# Schematic_Rev2.net
KiCad netlist of a schematic drawn in Altium Designer
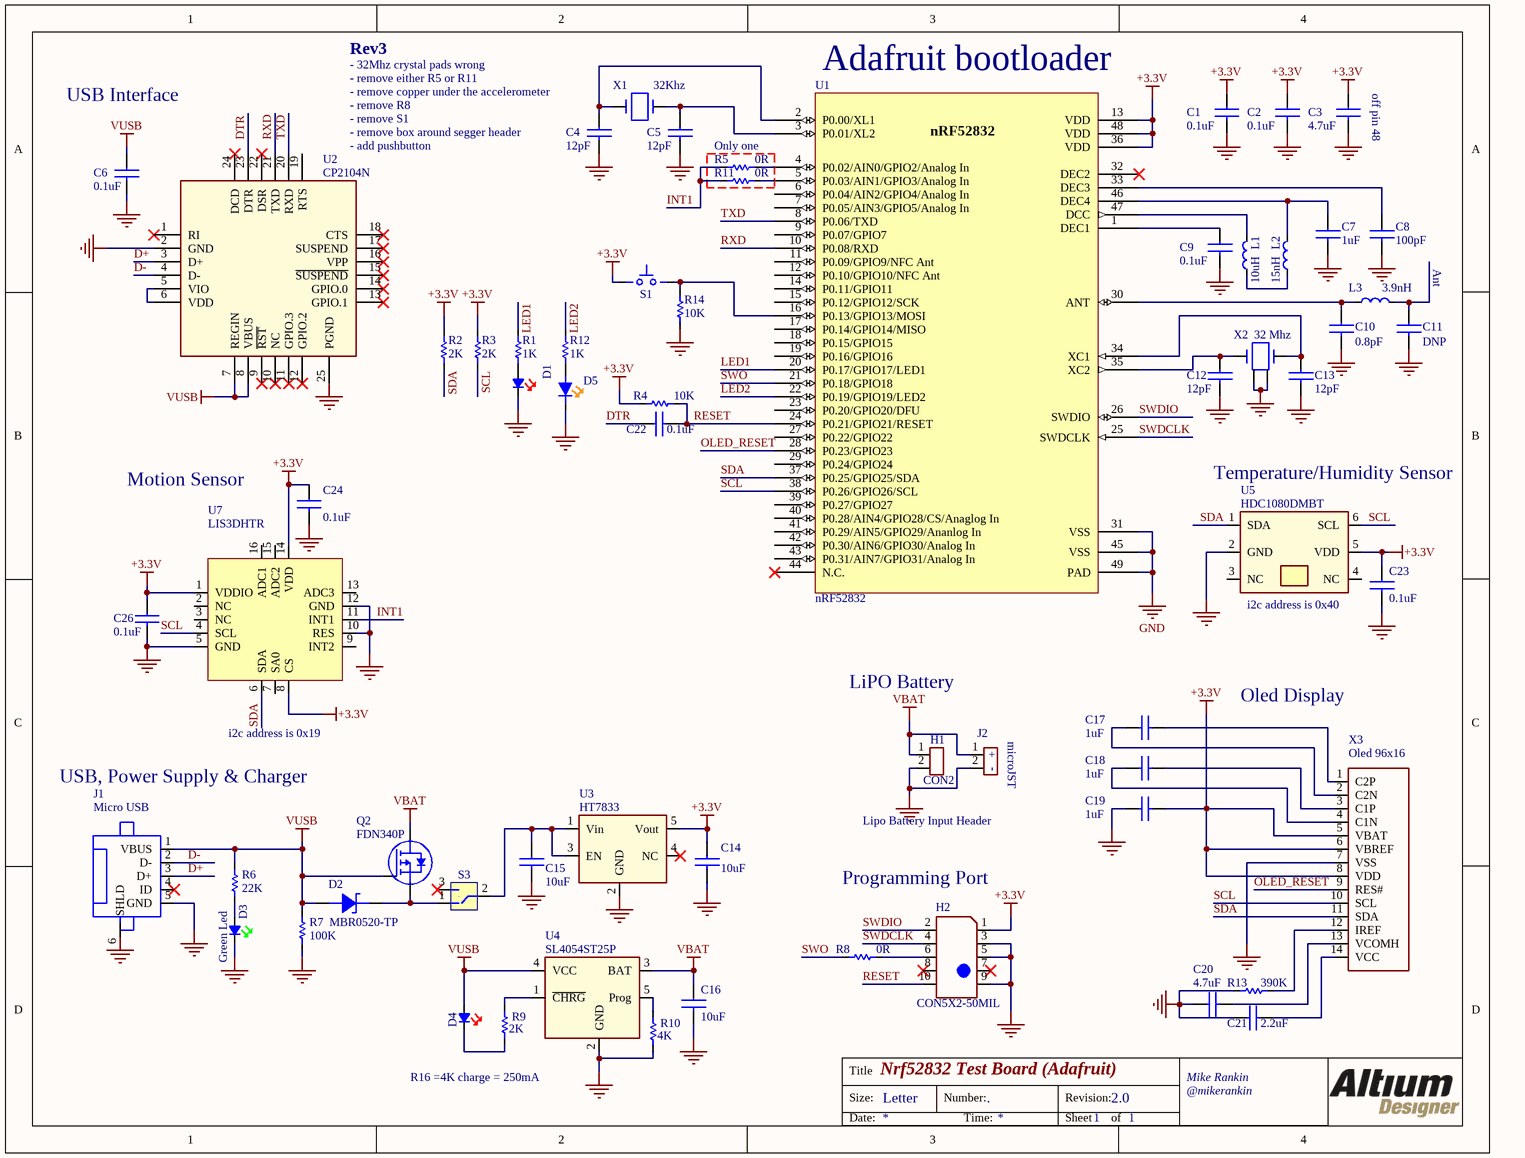
[diagram p0: Schematic_Rev2.SchDoc]

(export (version "E")
  (design (tool "Eeschema 10.0.6"))
  (components
    (comp (ref "C1")
      (value "0.1uF")
      (footprint "CAPC1005X56N")
      (description "CAP 0.1uF 0402")
      (libsource (lib "MAR") (part "CAP_0402"))
    )
    (comp (ref "C2")
      (value "0.1uF")
      (footprint "CAPC1005X56N")
      (description "CAP 0.1uF 0402")
      (libsource (lib "MAR") (part "CAP_0402"))
    )
    (comp (ref "C3")
      (value "4.7uF")
      (footprint "CAPC1005X56N")
      (description "CAP 4.7uF 0402")
      (libsource (lib "MAR") (part "CAP_0402"))
    )
    (comp (ref "C4")
      (value "12pF")
      (footprint "CAPC1005X56N")
      (description "CAP 12pF 0402")
      (libsource (lib "MAR") (part "CAP_0402"))
    )
    (comp (ref "C5")
      (value "12pF")
      (footprint "CAPC1005X56N")
      (description "CAP 12pF 0402")
      (libsource (lib "MAR") (part "CAP_0402"))
    )
    (comp (ref "C6")
      (value "0.1uF")
      (footprint "CAPC1005X56N")
      (description "CAP 0.1uF 0402")
      (libsource (lib "MAR") (part "CAP_0402"))
    )
    (comp (ref "C7")
      (value "1uF")
      (footprint "CAPC1005X56N")
      (description "CAP 1uF 0402")
      (libsource (lib "MAR") (part "CAP_0402"))
    )
    (comp (ref "C8")
      (value "100pF")
      (footprint "CAPC1005X56N")
      (description "CAP 100pF 0402")
      (libsource (lib "MAR") (part "CAP_0402"))
    )
    (comp (ref "C9")
      (value "0.1uF")
      (footprint "CAPC1005X56N")
      (description "CAP 0.1uF 0402")
      (libsource (lib "MAR") (part "CAP_0402"))
    )
    (comp (ref "C10")
      (value "0.8pF")
      (footprint "CAPC1005X56N")
      (description "CAP 0.8pF 0402")
      (libsource (lib "MAR") (part "CAP_0402"))
    )
    (comp (ref "C11")
      (value "DNP")
      (footprint "CAPC1005X56N")
      (description "CAP DNP 0402")
      (libsource (lib "MAR") (part "CAP_0402"))
    )
    (comp (ref "C12")
      (value "12pF")
      (footprint "CAPC1005X56N")
      (description "CAP 12pF 0402")
      (libsource (lib "MAR") (part "CAP_0402"))
    )
    (comp (ref "C13")
      (value "12pF")
      (footprint "CAPC1005X56N")
      (description "CAP 12pF 0402")
      (libsource (lib "MAR") (part "CAP_0402"))
    )
    (comp (ref "C14")
      (value "10uF")
      (footprint "CAPC2012X140N")
      (description "CAP 10uF 0805")
      (libsource (lib "MAR") (part "CAP_0805"))
    )
    (comp (ref "C15")
      (value "10uF")
      (footprint "CAPC2012X140N")
      (description "CAP 10uF 0805")
      (libsource (lib "MAR") (part "CAP_0805"))
    )
    (comp (ref "C16")
      (value "10uF")
      (footprint "CAPC2012X140N")
      (description "CAP 10uF 0805")
      (libsource (lib "MAR") (part "CAP_0805"))
    )
    (comp (ref "C17")
      (value "1uF")
      (footprint "CAPC1005X56N")
      (description "CAP 0.1uF 16V 0402")
      (fields (field (name "PART_NUMBER") "C29266") (field (name "MANUFACTURER") "Samsung"))
      (libsource (lib "MAR") (part "CAP_0402"))
    )
    (comp (ref "C18")
      (value "1uF")
      (footprint "CAPC1005X56N")
      (description "CAP 0.1uF 16V 0402")
      (fields (field (name "PART_NUMBER") "C29266") (field (name "MANUFACTURER") "Samsung"))
      (libsource (lib "MAR") (part "CAP_0402"))
    )
    (comp (ref "C19")
      (value "1uF")
      (footprint "CAPC1005X56N")
      (description "CAP 0.1uF 16V 0402")
      (fields (field (name "PART_NUMBER") "C29266") (field (name "MANUFACTURER") "Samsung"))
      (libsource (lib "MAR") (part "CAP_0402"))
    )
    (comp (ref "C20")
      (value "4.7uF")
      (footprint "CAPC1005X56N")
      (description "CAP 4.7uF 16V 0402")
      (fields (field (name "PART_NUMBER") "C318563") (field (name "MANUFACTURER") "Samsung"))
      (libsource (lib "MAR") (part "CAP_0402"))
    )
    (comp (ref "C21")
      (value "2.2uF")
      (footprint "CAPC1005X56N")
      (description "CAP 2.2uF 16V 0402")
      (fields (field (name "PART_NUMBER") "C170151") (field (name "MANUFACTURER") "Samsung"))
      (libsource (lib "MAR") (part "CAP_0402"))
    )
    (comp (ref "C22")
      (value "0.1uF")
      (footprint "CAPC1005X56N")
      (description "CAP 0.1uF 0402")
      (libsource (lib "MAR") (part "CAP_0402"))
    )
    (comp (ref "C23")
      (value "0.1uF")
      (footprint "CAPC1005X56N")
      (description "CAP 0.1uF 0402")
      (fields (field (name "PARTNUMBER") "TCC0402X5R104M160AT") (field (name "MANUFACTURER") "CCTC"))
      (libsource (lib "MAR") (part "CAP_0402"))
    )
    (comp (ref "C24")
      (value "0.1uF")
      (footprint "RESC1005X40L")
      (description "CAP 0.1uF 0402")
      (fields (field (name "PARTNUMBER") "C344190") (field (name "MANUFACTURER") "CCTC"))
      (libsource (lib "MAR") (part "CAP_0402"))
    )
    (comp (ref "C26")
      (value "0.1uF")
      (footprint "CAPC1005X56N")
      (description "CAP 0.1uF 0402")
      (fields (field (name "PARTNUMBER") "C344190") (field (name "MANUFACTURER") "CCTC"))
      (libsource (lib "MAR") (part "CAP_0402"))
    )
    (comp (ref "D1")
      (value "Red Led")
      (footprint "LED1608X55N-RED")
      (description "LED RED 0603")
      (libsource (lib "MAR") (part "LED_0603_SMALL_RED"))
    )
    (comp (ref "D2")
      (value "MBR0520-TP")
      (footprint "SOD123")
      (description "DIODE SCHOTTKY 20V 500MA SOD-123")
      (fields (field (name "MANUFACTURER") "Micro") (field (name "PART_NUMBER") "C78746"))
      (libsource (lib "MAR") (part "MBR0520-TP"))
    )
    (comp (ref "D3")
      (value "Green Led")
      (footprint "LED1608X55N-RED")
      (description "LED Green 0603")
      (libsource (lib "MAR") (part "LED_0603_SMALL_GREEN"))
    )
    (comp (ref "D4")
      (value "Red Led")
      (footprint "LED1608X55N-RED")
      (description "LED RED 0603")
      (libsource (lib "MAR") (part "LED_0603_SMALL_RED"))
    )
    (comp (ref "D5")
      (value "Orange Led")
      (footprint "LED1608X55N-YELLOW")
      (description "LED Orange 0603")
      (libsource (lib "MAR") (part "LED_0603_Orange"))
    )
    (comp (ref "H1")
      (value "CON2")
      (footprint "HDR1X2-EMPTY")
      (description "EMPTY SOLDER 2POS")
      (libsource (lib "MAR") (part "CON2-EMPTY_PAD"))
    )
    (comp (ref "H2")
      (value "CON5X2-50MIL")
      (footprint "HDR5X2-50MIL-SMT")
      (description "JTAG CONN HEADER 5X2POS 50mil\" PADS")
      (fields (field (name "PARTNUMBER") "PADS"))
      (libsource (lib "MAR") (part "CON5X2_50mil"))
    )
    (comp (ref "J1")
      (value "Micro USB")
      (footprint "U254-051N-4BH806")
      (description "CONN RECPT MICRO USB")
      (fields (field (name "MANUFACTURER") "XKB") (field (name "PART_NUMBER") "C319170"))
      (libsource (lib "MAR") (part "U254-051N-4BH806"))
    )
    (comp (ref "J2")
      (value "CON2")
      (footprint "JST_Micro_2PIN")
      (description "JST MIcro CONN 2POS")
      (libsource (lib "MAR") (part "JST_Micro_CONN_2PIN"))
    )
    (comp (ref "L1")
      (value "10uH")
      (footprint "RESC1608X06L")
      (description "INDUCTOR 10uH 900mA 0603")
      (fields (field (name "MANUFACTURER") "Murata"))
      (libsource (lib "MAR") (part "LQW15AN3N9D10D"))
    )
    (comp (ref "L2")
      (value "15nH")
      (footprint "INDC1005X40L")
      (description "INDUCTOR 15nH 900mA 0402")
      (libsource (lib "MAR") (part "LQW15AN3N9D10D"))
    )
    (comp (ref "L3")
      (value "3.9nH")
      (footprint "INDC1005X40L")
      (description "INDUCTOR 3.9nH 900mA 0402")
      (fields (field (name "PART_NUMBER") "C412344") (field (name "MANUFACTURER") "Murata"))
      (libsource (lib "MAR") (part "LQW15AN3N9D10D"))
    )
    (comp (ref "Q2")
      (value "FDN340P")
      (footprint "SOT95P240X110-3N")
      (description "MOSFET P-CH 20V 2A SOT-23")
      (fields (field (name "MANUFACTURER") "On Semi") (field (name "PART_NUMBER") "C75469"))
      (libsource (lib "MAR") (part "FDN340P"))
    )
    (comp (ref "R1")
      (value "1K")
      (footprint "RESC1005X40L")
      (description "RES 1K 0402")
      (libsource (lib "MAR") (part "RES_0402"))
    )
    (comp (ref "R2")
      (value "2K")
      (footprint "RESC1005X40L")
      (description "RES 2K 0402")
      (libsource (lib "MAR") (part "RES_0402"))
    )
    (comp (ref "R3")
      (value "2K")
      (footprint "RESC1005X40L")
      (description "RES 2K 0402")
      (libsource (lib "MAR") (part "RES_0402"))
    )
    (comp (ref "R4")
      (value "10K")
      (footprint "RESC1005X40L")
      (description "RES 10K 0402")
      (libsource (lib "MAR") (part "RES_0402"))
    )
    (comp (ref "R5")
      (value "0R")
      (footprint "RESC1005X40L")
      (description "RES 0R 0402")
      (libsource (lib "MAR") (part "RES_0402"))
    )
    (comp (ref "R6")
      (value "22K")
      (footprint "RESC1005X40L")
      (description "RES 22K 0402")
      (libsource (lib "MAR") (part "RES_0402"))
    )
    (comp (ref "R7")
      (value "100K")
      (footprint "RESC1005X40L")
      (description "RES 100K 0402")
      (libsource (lib "MAR") (part "RES_0402"))
    )
    (comp (ref "R8")
      (value "0R")
      (footprint "RESC1005X40L")
      (description "RES 0R 0402")
      (libsource (lib "MAR") (part "RES_0402"))
    )
    (comp (ref "R9")
      (value "2K")
      (footprint "RESC1005X40L")
      (description "RES 2K 0402")
      (libsource (lib "MAR") (part "RES_0402"))
    )
    (comp (ref "R10")
      (value "4K")
      (footprint "RESC1005X40L")
      (description "RES 4K 0402")
      (libsource (lib "MAR") (part "RES_0402"))
    )
    (comp (ref "R11")
      (value "0R")
      (footprint "RESC1005X40L")
      (description "RES 0R 0402")
      (libsource (lib "MAR") (part "RES_0402"))
    )
    (comp (ref "R12")
      (value "1K")
      (footprint "RESC1005X40L")
      (description "RES 1K 0402")
      (libsource (lib "MAR") (part "RES_0402"))
    )
    (comp (ref "R13")
      (value "390K")
      (footprint "RESC1005X40L")
      (description "RES 390K 0402")
      (fields (field (name "PART_NUMBER") "C25782") (field (name "MANUFACTURER") "Uniroyal"))
      (libsource (lib "MAR") (part "RES_0402"))
    )
    (comp (ref "R14")
      (value "10K")
      (footprint "RESC1005X40L")
      (description "RES 10K 0402")
      (libsource (lib "MAR") (part "RES_0402"))
    )
    (comp (ref "S1")
      (value "Pushbutton")
      (footprint "TL1015AF160QG")
      (description "Switch SMD,3x4x2.5mm")
      (fields (field (name "PART_NUMBER") "C455281") (field (name "MANUFACTURER") "Xunpu"))
      (libsource (lib "MAR") (part "TL1015AF160QG"))
    )
    (comp (ref "S3")
      (value "SWITCH SLIDE")
      (footprint "SK-3245D-02-L4")
      (description "Switch Slide Thu Hole")
      (fields (field (name "MANUFACTURER") "KXB Enterprise") (field (name "PARTNUMBER") "SK-3245D-02-L4"))
      (libsource (lib "MAR") (part "SK-3245D-02-L4"))
    )
    (comp (ref "U1")
      (value "nRF52832")
      (footprint "QFN48")
      (description "MCU Bluetooth 2.4GHz 48-VFQFN Exposed Pad")
      (fields (field (name "MANUFACTURER") "Nordic Semi") (field (name "PART_NUMBER") "C77540"))
      (libsource (lib "MAR") (part "nRF52832"))
    )
    (comp (ref "U2")
      (value "CP2104N")
      (footprint "24-QFN")
      (description "IC BRIDGE USB TO UART 24QFN")
      (fields (field (name "MANUFACTURER") "Silicon Labs") (field (name "PART_NUMBER") "C47742"))
      (libsource (lib "MAR") (part "CP2104-F03-GMR"))
    )
    (comp (ref "U3")
      (value "HT7833")
      (footprint "SOT95P280X144-5N")
      (description "IC LDO 3.3V 0.5A SOT23-5")
      (fields (field (name "MANUFACTURER") "Holtek") (field (name "PART_NUMBER") "C164106"))
      (libsource (lib "MAR") (part "HT7833"))
    )
    (comp (ref "U4")
      (value "SL4054ST25P")
      (footprint "SOT95P280X144-5N")
      (description "Charger IC Lithium-Ion/Polymer SOT23-5")
      (fields (field (name "MANUFACTURER") "Techfuse") (field (name "PARTNUMBER") "C258510"))
      (libsource (lib "MAR") (part "SL4054ST25P"))
    )
    (comp (ref "U5")
      (value "HDC1080DMBT")
      (footprint "HDC1080")
      (description "Humidity/Temperature Sensor")
      (fields (field (name "MANUFACTURER") "Texas Instruments") (field (name "PARTNUMBER") "HDC1080DMBT"))
      (libsource (lib "MAR") (part "HDC1080DMBT"))
    )
    (comp (ref "U7")
      (value "LIS3DHTR")
      (footprint "QFN3X3_16_1.2")
      (description "IC ACCEL 2-16G I2C/SPI 16LGA")
      (fields (field (name "PARTNUMBER") "C15134") (field (name "MANUFACTURER") "STMicro"))
      (libsource (lib "ACPartNumbers") (part "E-05-177"))
    )
    (comp (ref "X1")
      (value "32Khz")
      (footprint "ECS-.327-12.5-34B")
      (description "CRYSTAL 32.768 KHZ 12.5PF SMD")
      (fields (field (name "PART_NUMBER") "ECS-.327-12.5-34B") (field (name "MANUFACTURER") "ECS"))
      (libsource (lib "MAR") (part "ECS-.327-12.5-34B"))
    )
    (comp (ref "X2")
      (value "32 Mhz")
      (footprint "OSC20X16")
      (description "CRYSTAL 32MHZ 12PF SMD")
      (fields (field (name "PART_NUMBER") "8Y32000001") (field (name "MANUFACTURER") "TXC Corp"))
      (libsource (lib "MAR") (part "32Mhz"))
    )
    (comp (ref "X3")
      (value "OLED_GLASS 96x16")
      (footprint "OLED_GLASS 96x16")
      (description "96x16 OLED_GLASS")
      (fields (field (name "PART_NUMBER") "ER-OLED0.69-1W"))
      (libsource (lib "MAR") (part "OLED_GLASS 96x16"))
    )
  )
  (nets
    (net (code "1") (name "+3.3V") (class "Default")
      (node (ref "C1") (pin "1") (pinfunction "1_1") (pintype "passive"))
      (node (ref "C14") (pin "1") (pinfunction "1_1") (pintype "passive"))
      (node (ref "C19") (pin "2") (pinfunction "2_2") (pintype "passive"))
      (node (ref "C2") (pin "1") (pinfunction "1_1") (pintype "passive"))
      (node (ref "C23") (pin "1") (pinfunction "1_1") (pintype "passive"))
      (node (ref "C24") (pin "1") (pinfunction "1_1") (pintype "passive"))
      (node (ref "C26") (pin "1") (pinfunction "1_1") (pintype "passive"))
      (node (ref "C3") (pin "1") (pinfunction "1_1") (pintype "passive"))
      (node (ref "H2") (pin "1") (pintype "passive"))
      (node (ref "R2") (pin "2") (pintype "passive"))
      (node (ref "R3") (pin "2") (pintype "passive"))
      (node (ref "R4") (pin "2") (pintype "passive"))
      (node (ref "S1") (pin "1") (pinfunction "A_1") (pintype "passive"))
      (node (ref "U1") (pin "13") (pinfunction "VDD_13") (pintype "power_in"))
      (node (ref "U1") (pin "36") (pinfunction "VDD_36") (pintype "power_in"))
      (node (ref "U1") (pin "48") (pinfunction "VDD_48") (pintype "power_in"))
      (node (ref "U3") (pin "5") (pinfunction "Vout_5") (pintype "passive"))
      (node (ref "U5") (pin "5") (pinfunction "VDD_5") (pintype "power_in"))
      (node (ref "U7") (pin "1") (pinfunction "VDDIO_1") (pintype "power_in"))
      (node (ref "U7") (pin "14") (pinfunction "VDD_14") (pintype "power_in"))
      (node (ref "U7") (pin "8") (pinfunction "CS_8") (pintype "passive"))
      (node (ref "X3") (pin "5") (pinfunction "VBAT_5") (pintype "passive"))
      (node (ref "X3") (pin "6") (pinfunction "VBREF_6") (pintype "passive"))
      (node (ref "X3") (pin "8") (pinfunction "VDD_8") (pintype "passive"))
    )
    (net (code "2") (name "/D+") (class "Default")
      (node (ref "J1") (pin "3") (pinfunction "D+_3") (pintype "passive"))
      (node (ref "U2") (pin "3") (pinfunction "D+_3") (pintype "passive"))
    )
    (net (code "3") (name "/D-") (class "Default")
      (node (ref "J1") (pin "2") (pinfunction "D-_2") (pintype "passive"))
      (node (ref "U2") (pin "4") (pinfunction "D-_4") (pintype "passive"))
    )
    (net (code "4") (name "/DTR") (class "Default")
      (node (ref "C22") (pin "1") (pinfunction "1_1") (pintype "passive"))
      (node (ref "U2") (pin "23") (pinfunction "DTR_23") (pintype "passive"))
    )
    (net (code "5") (name "/INT1") (class "Default")
      (node (ref "R11") (pin "2") (pintype "passive"))
      (node (ref "R5") (pin "2") (pintype "passive"))
      (node (ref "U7") (pin "11") (pinfunction "INT1_11") (pintype "passive"))
    )
    (net (code "6") (name "/LED1") (class "Default")
      (node (ref "R1") (pin "2") (pintype "passive"))
      (node (ref "U1") (pin "20") (pinfunction "P0.17/GPIO17/LED1_20") (pintype "bidirectional"))
    )
    (net (code "7") (name "/LED2") (class "Default")
      (node (ref "R12") (pin "2") (pintype "passive"))
      (node (ref "U1") (pin "22") (pinfunction "P0.19/GPIO19/LED2_22") (pintype "bidirectional"))
    )
    (net (code "8") (name "/OLED_RESET") (class "Default")
      (node (ref "U1") (pin "28") (pinfunction "P0.23/GPIO23_28") (pintype "bidirectional"))
      (node (ref "X3") (pin "9") (pinfunction "RES#_9") (pintype "passive"))
    )
    (net (code "9") (name "/RESET") (class "Default")
      (node (ref "C22") (pin "2") (pinfunction "2_2") (pintype "passive"))
      (node (ref "H2") (pin "10") (pintype "passive"))
      (node (ref "R4") (pin "1") (pintype "passive"))
      (node (ref "U1") (pin "24") (pinfunction "P0.21/GPIO21/RESET_24") (pintype "bidirectional"))
    )
    (net (code "10") (name "/RXD") (class "Default")
      (node (ref "U1") (pin "10") (pinfunction "P0.08/RXD_10") (pintype "bidirectional"))
      (node (ref "U2") (pin "21") (pinfunction "TXD_21") (pintype "passive"))
    )
    (net (code "11") (name "/SCL") (class "Default")
      (node (ref "R3") (pin "1") (pintype "passive"))
      (node (ref "U1") (pin "38") (pinfunction "P0.26/GPIO26/SCL_38") (pintype "bidirectional"))
      (node (ref "U5") (pin "6") (pinfunction "SCL_6") (pintype "passive"))
      (node (ref "U7") (pin "4") (pinfunction "SCL_4") (pintype "passive"))
      (node (ref "X3") (pin "10") (pinfunction "SCL_10") (pintype "passive"))
    )
    (net (code "12") (name "/SDA") (class "Default")
      (node (ref "R2") (pin "1") (pintype "passive"))
      (node (ref "U1") (pin "37") (pinfunction "P0.25/GPIO25/SDA_37") (pintype "bidirectional"))
      (node (ref "U5") (pin "1") (pinfunction "SDA_1") (pintype "passive"))
      (node (ref "U7") (pin "6") (pinfunction "SDA_6") (pintype "passive"))
      (node (ref "X3") (pin "11") (pinfunction "SDA_11") (pintype "passive"))
    )
    (net (code "13") (name "/SWDCLK") (class "Default")
      (node (ref "H2") (pin "4") (pintype "passive"))
      (node (ref "U1") (pin "25") (pinfunction "SWDCLK_25") (pintype "input"))
    )
    (net (code "14") (name "/SWDIO") (class "Default")
      (node (ref "H2") (pin "2") (pintype "passive"))
      (node (ref "U1") (pin "26") (pinfunction "SWDIO_26") (pintype "bidirectional"))
    )
    (net (code "15") (name "/SWO") (class "Default")
      (node (ref "R8") (pin "1") (pintype "passive"))
      (node (ref "U1") (pin "21") (pinfunction "P0.18/GPIO18_21") (pintype "bidirectional"))
    )
    (net (code "16") (name "/TXD") (class "Default")
      (node (ref "U1") (pin "8") (pinfunction "P0.06/TXD_8") (pintype "bidirectional"))
      (node (ref "U2") (pin "20") (pinfunction "RXD_20") (pintype "passive"))
    )
    (net (code "17") (name "GND") (class "Default")
      (node (ref "C1") (pin "2") (pinfunction "2_2") (pintype "passive"))
      (node (ref "C10") (pin "2") (pinfunction "2_2") (pintype "passive"))
      (node (ref "C11") (pin "2") (pinfunction "2_2") (pintype "passive"))
      (node (ref "C12") (pin "2") (pinfunction "2_2") (pintype "passive"))
      (node (ref "C13") (pin "2") (pinfunction "2_2") (pintype "passive"))
      (node (ref "C14") (pin "2") (pinfunction "2_2") (pintype "passive"))
      (node (ref "C15") (pin "2") (pinfunction "2_2") (pintype "passive"))
      (node (ref "C16") (pin "2") (pinfunction "2_2") (pintype "passive"))
      (node (ref "C19") (pin "1") (pinfunction "1_1") (pintype "passive"))
      (node (ref "C2") (pin "2") (pinfunction "2_2") (pintype "passive"))
      (node (ref "C20") (pin "1") (pinfunction "1_1") (pintype "passive"))
      (node (ref "C21") (pin "1") (pinfunction "1_1") (pintype "passive"))
      (node (ref "C23") (pin "2") (pinfunction "2_2") (pintype "passive"))
      (node (ref "C24") (pin "2") (pinfunction "2_2") (pintype "passive"))
      (node (ref "C26") (pin "2") (pinfunction "2_2") (pintype "passive"))
      (node (ref "C3") (pin "2") (pinfunction "2_2") (pintype "passive"))
      (node (ref "C4") (pin "2") (pinfunction "2_2") (pintype "passive"))
      (node (ref "C5") (pin "2") (pinfunction "2_2") (pintype "passive"))
      (node (ref "C6") (pin "2") (pinfunction "2_2") (pintype "passive"))
      (node (ref "C7") (pin "2") (pinfunction "2_2") (pintype "passive"))
      (node (ref "C8") (pin "2") (pinfunction "2_2") (pintype "passive"))
      (node (ref "C9") (pin "2") (pinfunction "2_2") (pintype "passive"))
      (node (ref "D1") (pin "1") (pintype "passive"))
      (node (ref "D3") (pin "1") (pintype "passive"))
      (node (ref "D5") (pin "1") (pintype "passive"))
      (node (ref "H1") (pin "2") (pintype "passive"))
      (node (ref "H2") (pin "3") (pintype "passive"))
      (node (ref "H2") (pin "5") (pintype "passive"))
      (node (ref "H2") (pin "9") (pintype "passive"))
      (node (ref "J1") (pin "5") (pinfunction "GND_5") (pintype "power_in"))
      (node (ref "J1") (pin "6") (pinfunction "SHLD_6") (pintype "power_in"))
      (node (ref "J2") (pin "2") (pintype "passive"))
      (node (ref "R10") (pin "1") (pintype "passive"))
      (node (ref "R13") (pin "1") (pintype "passive"))
      (node (ref "R14") (pin "2") (pintype "passive"))
      (node (ref "R7") (pin "1") (pintype "passive"))
      (node (ref "U1") (pin "31") (pinfunction "VSS_31") (pintype "power_in"))
      (node (ref "U1") (pin "45") (pinfunction "VSS_45") (pintype "power_in"))
      (node (ref "U1") (pin "49") (pinfunction "PAD_49") (pintype "power_in"))
      (node (ref "U2") (pin "2") (pinfunction "GND_2") (pintype "power_in"))
      (node (ref "U2") (pin "25") (pinfunction "PGND_25") (pintype "passive"))
      (node (ref "U3") (pin "2") (pinfunction "GND_2") (pintype "power_in"))
      (node (ref "U4") (pin "2") (pinfunction "GND_2") (pintype "power_in"))
      (node (ref "U5") (pin "2") (pinfunction "GND_2") (pintype "power_in"))
      (node (ref "U7") (pin "10") (pinfunction "RES_10") (pintype "passive"))
      (node (ref "U7") (pin "12") (pinfunction "GND_12") (pintype "power_in"))
      (node (ref "U7") (pin "5") (pinfunction "GND_5") (pintype "power_in"))
      (node (ref "X2") (pin "2") (pinfunction "2_2") (pintype "power_in"))
      (node (ref "X2") (pin "4") (pinfunction "4_4") (pintype "power_in"))
      (node (ref "X3") (pin "7") (pinfunction "VSS_7") (pintype "passive"))
    )
    (net (code "18") (name "Net-(C11-Pad1)") (class "Default")
      (node (ref "C11") (pin "1") (pinfunction "1_1") (pintype "passive"))
      (node (ref "L3") (pin "2") (pinfunction "2_2") (pintype "passive"))
    )
    (net (code "19") (name "Net-(D1-Pad2)") (class "Default")
      (node (ref "D1") (pin "2") (pintype "passive"))
      (node (ref "R1") (pin "1") (pintype "passive"))
    )
    (net (code "20") (name "Net-(D2-Cathode)") (class "Default")
      (node (ref "D2") (pin "1") (pinfunction "Cathode_1") (pintype "passive"))
      (node (ref "Q2") (pin "2") (pinfunction "S_2") (pintype "passive"))
      (node (ref "S3") (pin "1") (pinfunction "1_1") (pintype "passive"))
    )
    (net (code "21") (name "Net-(D3-Pad2)") (class "Default")
      (node (ref "D3") (pin "2") (pintype "passive"))
      (node (ref "R6") (pin "1") (pintype "passive"))
    )
    (net (code "22") (name "Net-(D4-Pad1)") (class "Default")
      (node (ref "D4") (pin "1") (pintype "passive"))
      (node (ref "R9") (pin "1") (pintype "passive"))
    )
    (net (code "23") (name "Net-(D5-Pad2)") (class "Default")
      (node (ref "D5") (pin "2") (pintype "passive"))
      (node (ref "R12") (pin "1") (pintype "passive"))
    )
    (net (code "24") (name "Net-(H2-Pad6)") (class "Default")
      (node (ref "H2") (pin "6") (pintype "passive"))
      (node (ref "R8") (pin "2") (pintype "passive"))
    )
    (net (code "25") (name "Net-(L1-Pad1)") (class "Default")
      (node (ref "L1") (pin "1") (pinfunction "1_1") (pintype "passive"))
      (node (ref "L2") (pin "1") (pinfunction "1_1") (pintype "passive"))
    )
    (net (code "26") (name "Net-(S1-B)") (class "Default")
      (node (ref "R14") (pin "1") (pintype "passive"))
      (node (ref "S1") (pin "2") (pinfunction "B_2") (pintype "passive"))
      (node (ref "U1") (pin "16") (pinfunction "P0.13/GPIO13/MOSI_16") (pintype "bidirectional"))
    )
    (net (code "27") (name "Net-(U1-ANT)") (class "Default")
      (node (ref "C10") (pin "1") (pinfunction "1_1") (pintype "passive"))
      (node (ref "L3") (pin "1") (pinfunction "1_1") (pintype "passive"))
      (node (ref "U1") (pin "30") (pinfunction "ANT_30") (pintype "bidirectional"))
    )
    (net (code "28") (name "Net-(U1-DCC)") (class "Default")
      (node (ref "L1") (pin "2") (pinfunction "2_2") (pintype "passive"))
      (node (ref "U1") (pin "47") (pinfunction "DCC_47") (pintype "output"))
    )
    (net (code "29") (name "Net-(U1-DEC1)") (class "Default")
      (node (ref "C9") (pin "1") (pinfunction "1_1") (pintype "passive"))
      (node (ref "U1") (pin "1") (pinfunction "DEC1_1") (pintype "power_in"))
    )
    (net (code "30") (name "Net-(U1-DEC3)") (class "Default")
      (node (ref "C8") (pin "1") (pinfunction "1_1") (pintype "passive"))
      (node (ref "U1") (pin "33") (pinfunction "DEC3_33") (pintype "power_in"))
    )
    (net (code "31") (name "Net-(U1-DEC4)") (class "Default")
      (node (ref "C7") (pin "1") (pinfunction "1_1") (pintype "passive"))
      (node (ref "L2") (pin "2") (pinfunction "2_2") (pintype "passive"))
      (node (ref "U1") (pin "46") (pinfunction "DEC4_46") (pintype "power_in"))
    )
    (net (code "32") (name "Net-(U1-P0.00{slash}XL1)") (class "Default")
      (node (ref "C4") (pin "1") (pinfunction "1_1") (pintype "passive"))
      (node (ref "U1") (pin "2") (pinfunction "P0.00/XL1_2") (pintype "bidirectional"))
      (node (ref "X1") (pin "1") (pinfunction "1_1") (pintype "passive"))
    )
    (net (code "33") (name "Net-(U1-P0.01{slash}XL2)") (class "Default")
      (node (ref "C5") (pin "1") (pinfunction "1_1") (pintype "passive"))
      (node (ref "U1") (pin "3") (pinfunction "P0.01/XL2_3") (pintype "bidirectional"))
      (node (ref "X1") (pin "2") (pinfunction "2_2") (pintype "passive"))
    )
    (net (code "34") (name "Net-(U1-P0.02{slash}AIN0{slash}GPIO2{slash}Analog_In)") (class "Default")
      (node (ref "R5") (pin "1") (pintype "passive"))
      (node (ref "U1") (pin "4") (pinfunction "P0.02/AIN0/GPIO2/Analog_In_4") (pintype "bidirectional"))
    )
    (net (code "35") (name "Net-(U1-P0.03{slash}AIN1{slash}GPIO3{slash}Analog_In)") (class "Default")
      (node (ref "R11") (pin "1") (pintype "passive"))
      (node (ref "U1") (pin "5") (pinfunction "P0.03/AIN1/GPIO3/Analog_In_5") (pintype "bidirectional"))
    )
    (net (code "36") (name "Net-(U1-XC1)") (class "Default")
      (node (ref "C13") (pin "1") (pinfunction "1_1") (pintype "passive"))
      (node (ref "U1") (pin "34") (pinfunction "XC1_34") (pintype "input"))
      (node (ref "X2") (pin "3") (pinfunction "3_3") (pintype "passive"))
    )
    (net (code "37") (name "Net-(U1-XC2)") (class "Default")
      (node (ref "C12") (pin "1") (pinfunction "1_1") (pintype "passive"))
      (node (ref "U1") (pin "35") (pinfunction "XC2_35") (pintype "output"))
      (node (ref "X2") (pin "1") (pinfunction "1_1") (pintype "passive"))
    )
    (net (code "38") (name "Net-(U2-VDD)") (class "Default")
      (node (ref "U2") (pin "5") (pinfunction "VIO_5") (pintype "power_in"))
      (node (ref "U2") (pin "6") (pinfunction "VDD_6") (pintype "power_in"))
    )
    (net (code "39") (name "Net-(U3-EN)") (class "Default")
      (node (ref "C15") (pin "1") (pinfunction "1_1") (pintype "passive"))
      (node (ref "S3") (pin "2") (pinfunction "2_2") (pintype "passive"))
      (node (ref "U3") (pin "1") (pinfunction "Vin_1") (pintype "passive"))
      (node (ref "U3") (pin "3") (pinfunction "EN_3") (pintype "passive"))
    )
    (net (code "40") (name "Net-(U4-Prog)") (class "Default")
      (node (ref "R10") (pin "2") (pintype "passive"))
      (node (ref "U4") (pin "5") (pinfunction "Prog_5") (pintype "passive"))
    )
    (net (code "41") (name "Net-(U4-~{CHRG})") (class "Default")
      (node (ref "R9") (pin "2") (pintype "passive"))
      (node (ref "U4") (pin "1") (pinfunction "~{CHRG}_1") (pintype "passive"))
    )
    (net (code "42") (name "Net-(X3-C1N)") (class "Default")
      (node (ref "C18") (pin "1") (pinfunction "1_1") (pintype "passive"))
      (node (ref "X3") (pin "4") (pinfunction "C1N_4") (pintype "passive"))
    )
    (net (code "43") (name "Net-(X3-C1P)") (class "Default")
      (node (ref "C18") (pin "2") (pinfunction "2_2") (pintype "passive"))
      (node (ref "X3") (pin "3") (pinfunction "C1P_3") (pintype "passive"))
    )
    (net (code "44") (name "Net-(X3-C2N)") (class "Default")
      (node (ref "C17") (pin "1") (pinfunction "1_1") (pintype "passive"))
      (node (ref "X3") (pin "2") (pinfunction "C2N_2") (pintype "passive"))
    )
    (net (code "45") (name "Net-(X3-C2P)") (class "Default")
      (node (ref "C17") (pin "2") (pinfunction "2_2") (pintype "passive"))
      (node (ref "X3") (pin "1") (pinfunction "C2P_1") (pintype "passive"))
    )
    (net (code "46") (name "Net-(X3-IREF)") (class "Default")
      (node (ref "R13") (pin "2") (pintype "passive"))
      (node (ref "X3") (pin "12") (pinfunction "IREF_12") (pintype "passive"))
    )
    (net (code "47") (name "Net-(X3-VCC)") (class "Default")
      (node (ref "C21") (pin "2") (pinfunction "2_2") (pintype "passive"))
      (node (ref "X3") (pin "14") (pinfunction "VCC_14") (pintype "passive"))
    )
    (net (code "48") (name "Net-(X3-VCOMH)") (class "Default")
      (node (ref "C20") (pin "2") (pinfunction "2_2") (pintype "passive"))
      (node (ref "X3") (pin "13") (pinfunction "VCOMH_13") (pintype "passive"))
    )
    (net (code "49") (name "VBAT") (class "Default")
      (node (ref "C16") (pin "1") (pinfunction "1_1") (pintype "passive"))
      (node (ref "H1") (pin "1") (pintype "passive"))
      (node (ref "J2") (pin "1") (pintype "passive"))
      (node (ref "Q2") (pin "3") (pinfunction "D_3") (pintype "passive"))
      (node (ref "U4") (pin "3") (pinfunction "BAT_3") (pintype "passive"))
    )
    (net (code "50") (name "VUSB") (class "Default")
      (node (ref "C6") (pin "1") (pinfunction "1_1") (pintype "passive"))
      (node (ref "D2") (pin "2") (pinfunction "Annode_2") (pintype "passive"))
      (node (ref "D4") (pin "2") (pintype "passive"))
      (node (ref "J1") (pin "1") (pinfunction "VBUS_1") (pintype "power_in"))
      (node (ref "Q2") (pin "1") (pinfunction "G_1") (pintype "passive"))
      (node (ref "R6") (pin "2") (pintype "passive"))
      (node (ref "R7") (pin "2") (pintype "passive"))
      (node (ref "U2") (pin "7") (pinfunction "REGIN_7") (pintype "power_in"))
      (node (ref "U2") (pin "8") (pinfunction "VBUS_8") (pintype "power_in"))
      (node (ref "U4") (pin "4") (pinfunction "VCC_4") (pintype "passive"))
    )
    (net (code "51") (name "unconnected-(H2-Pad7)") (class "Default")
      (node (ref "H2") (pin "7") (pintype "passive+no_connect"))
    )
    (net (code "52") (name "unconnected-(H2-Pad8)") (class "Default")
      (node (ref "H2") (pin "8") (pintype "passive+no_connect"))
    )
    (net (code "53") (name "unconnected-(J1-ID-Pad4)") (class "Default")
      (node (ref "J1") (pin "4") (pinfunction "ID_4") (pintype "passive+no_connect"))
    )
    (net (code "54") (name "unconnected-(S3-Pad3)") (class "Default")
      (node (ref "S3") (pin "3") (pinfunction "3_3") (pintype "passive+no_connect"))
    )
    (net (code "55") (name "unconnected-(U1-DEC2-Pad32)") (class "Default")
      (node (ref "U1") (pin "32") (pinfunction "DEC2_32") (pintype "power_in+no_connect"))
    )
    (net (code "56") (name "unconnected-(U1-N.C.-Pad44)") (class "Default")
      (node (ref "U1") (pin "44") (pinfunction "N.C._44") (pintype "power_in+no_connect"))
    )
    (net (code "57") (name "unconnected-(U1-P0.04{slash}AIN2{slash}GPIO4{slash}Analog_In-Pad6)") (class "Default")
      (node (ref "U1") (pin "6") (pinfunction "P0.04/AIN2/GPIO4/Analog_In_6") (pintype "bidirectional"))
    )
    (net (code "58") (name "unconnected-(U1-P0.05{slash}AIN3{slash}GPIO5{slash}Analog_In-Pad7)") (class "Default")
      (node (ref "U1") (pin "7") (pinfunction "P0.05/AIN3/GPIO5/Analog_In_7") (pintype "bidirectional"))
    )
    (net (code "59") (name "unconnected-(U1-P0.07{slash}GPIO7-Pad9)") (class "Default")
      (node (ref "U1") (pin "9") (pinfunction "P0.07/GPIO7_9") (pintype "bidirectional"))
    )
    (net (code "60") (name "unconnected-(U1-P0.09{slash}GPIO9{slash}NFC_Ant-Pad11)") (class "Default")
      (node (ref "U1") (pin "11") (pinfunction "P0.09/GPIO9/NFC_Ant_11") (pintype "bidirectional"))
    )
    (net (code "61") (name "unconnected-(U1-P0.10{slash}GPIO10{slash}NFC_Ant-Pad12)") (class "Default")
      (node (ref "U1") (pin "12") (pinfunction "P0.10/GPIO10/NFC_Ant_12") (pintype "bidirectional"))
    )
    (net (code "62") (name "unconnected-(U1-P0.11{slash}GPIO11-Pad14)") (class "Default")
      (node (ref "U1") (pin "14") (pinfunction "P0.11/GPIO11_14") (pintype "bidirectional"))
    )
    (net (code "63") (name "unconnected-(U1-P0.12{slash}GPIO12{slash}SCK-Pad15)") (class "Default")
      (node (ref "U1") (pin "15") (pinfunction "P0.12/GPIO12/SCK_15") (pintype "bidirectional"))
    )
    (net (code "64") (name "unconnected-(U1-P0.14{slash}GPIO14{slash}MISO-Pad17)") (class "Default")
      (node (ref "U1") (pin "17") (pinfunction "P0.14/GPIO14/MISO_17") (pintype "bidirectional"))
    )
    (net (code "65") (name "unconnected-(U1-P0.15{slash}GPIO15-Pad18)") (class "Default")
      (node (ref "U1") (pin "18") (pinfunction "P0.15/GPIO15_18") (pintype "bidirectional"))
    )
    (net (code "66") (name "unconnected-(U1-P0.16{slash}GPIO16-Pad19)") (class "Default")
      (node (ref "U1") (pin "19") (pinfunction "P0.16/GPIO16_19") (pintype "bidirectional"))
    )
    (net (code "67") (name "unconnected-(U1-P0.20{slash}GPIO20{slash}DFU-Pad23)") (class "Default")
      (node (ref "U1") (pin "23") (pinfunction "P0.20/GPIO20/DFU_23") (pintype "bidirectional"))
    )
    (net (code "68") (name "unconnected-(U1-P0.22{slash}GPIO22-Pad27)") (class "Default")
      (node (ref "U1") (pin "27") (pinfunction "P0.22/GPIO22_27") (pintype "bidirectional"))
    )
    (net (code "69") (name "unconnected-(U1-P0.24{slash}GPIO24-Pad29)") (class "Default")
      (node (ref "U1") (pin "29") (pinfunction "P0.24/GPIO24_29") (pintype "bidirectional"))
    )
    (net (code "70") (name "unconnected-(U1-P0.27{slash}GPIO27-Pad39)") (class "Default")
      (node (ref "U1") (pin "39") (pinfunction "P0.27/GPIO27_39") (pintype "bidirectional"))
    )
    (net (code "71") (name "unconnected-(U1-P0.28{slash}AIN4{slash}GPIO28{slash}CS{slash}Anaglog_In-Pad40)") (class "Default")
      (node (ref "U1") (pin "40") (pinfunction "P0.28/AIN4/GPIO28/CS/Anaglog_In_40") (pintype "bidirectional"))
    )
    (net (code "72") (name "unconnected-(U1-P0.29{slash}AIN5{slash}GPIO29{slash}Ananlog_In-Pad41)") (class "Default")
      (node (ref "U1") (pin "41") (pinfunction "P0.29/AIN5/GPIO29/Ananlog_In_41") (pintype "bidirectional"))
    )
    (net (code "73") (name "unconnected-(U1-P0.30{slash}AIN6{slash}GPIO30{slash}Analog_In-Pad42)") (class "Default")
      (node (ref "U1") (pin "42") (pinfunction "P0.30/AIN6/GPIO30/Analog_In_42") (pintype "bidirectional"))
    )
    (net (code "74") (name "unconnected-(U1-P0.31{slash}AIN7{slash}GPIO31{slash}Analog_In-Pad43)") (class "Default")
      (node (ref "U1") (pin "43") (pinfunction "P0.31/AIN7/GPIO31/Analog_In_43") (pintype "bidirectional"))
    )
    (net (code "75") (name "unconnected-(U2-CTS-Pad18)") (class "Default")
      (node (ref "U2") (pin "18") (pinfunction "CTS_18") (pintype "passive+no_connect"))
    )
    (net (code "76") (name "unconnected-(U2-DCD-Pad24)") (class "Default")
      (node (ref "U2") (pin "24") (pinfunction "DCD_24") (pintype "passive+no_connect"))
    )
    (net (code "77") (name "unconnected-(U2-DSR-Pad22)") (class "Default")
      (node (ref "U2") (pin "22") (pinfunction "DSR_22") (pintype "passive+no_connect"))
    )
    (net (code "78") (name "unconnected-(U2-GPIO.0-Pad14)") (class "Default")
      (node (ref "U2") (pin "14") (pinfunction "GPIO.0_14") (pintype "passive+no_connect"))
    )
    (net (code "79") (name "unconnected-(U2-GPIO.1-Pad13)") (class "Default")
      (node (ref "U2") (pin "13") (pinfunction "GPIO.1_13") (pintype "passive+no_connect"))
    )
    (net (code "80") (name "unconnected-(U2-GPIO.2-Pad12)") (class "Default")
      (node (ref "U2") (pin "12") (pinfunction "GPIO.2_12") (pintype "passive+no_connect"))
    )
    (net (code "81") (name "unconnected-(U2-GPIO.3-Pad11)") (class "Default")
      (node (ref "U2") (pin "11") (pinfunction "GPIO.3_11") (pintype "passive+no_connect"))
    )
    (net (code "82") (name "unconnected-(U2-NC-Pad10)") (class "Default")
      (node (ref "U2") (pin "10") (pinfunction "NC_10") (pintype "passive+no_connect"))
    )
    (net (code "83") (name "unconnected-(U2-RI-Pad1)") (class "Default")
      (node (ref "U2") (pin "1") (pinfunction "RI_1") (pintype "passive+no_connect"))
    )
    (net (code "84") (name "unconnected-(U2-RTS-Pad19)") (class "Default")
      (node (ref "U2") (pin "19") (pinfunction "RTS_19") (pintype "passive"))
    )
    (net (code "85") (name "unconnected-(U2-SUSPEND-Pad17)") (class "Default")
      (node (ref "U2") (pin "17") (pinfunction "SUSPEND_17") (pintype "passive+no_connect"))
    )
    (net (code "86") (name "unconnected-(U2-VPP-Pad16)") (class "Default")
      (node (ref "U2") (pin "16") (pinfunction "VPP_16") (pintype "passive+no_connect"))
    )
    (net (code "87") (name "unconnected-(U2-~{RST}-Pad9)") (class "Default")
      (node (ref "U2") (pin "9") (pinfunction "~{RST}_9") (pintype "passive+no_connect"))
    )
    (net (code "88") (name "unconnected-(U2-~{SUSPEND}-Pad15)") (class "Default")
      (node (ref "U2") (pin "15") (pinfunction "~{SUSPEND}_15") (pintype "passive+no_connect"))
    )
    (net (code "89") (name "unconnected-(U3-NC-Pad4)") (class "Default")
      (node (ref "U3") (pin "4") (pinfunction "NC_4") (pintype "passive+no_connect"))
    )
    (net (code "90") (name "unconnected-(U5-NC-Pad3)") (class "Default")
      (node (ref "U5") (pin "3") (pinfunction "NC_3") (pintype "passive"))
    )
    (net (code "91") (name "unconnected-(U5-NC-Pad4)") (class "Default")
      (node (ref "U5") (pin "4") (pinfunction "NC_4") (pintype "passive"))
    )
    (net (code "92") (name "unconnected-(U7-ADC1-Pad16)") (class "Default")
      (node (ref "U7") (pin "16") (pinfunction "ADC1_16") (pintype "passive"))
    )
    (net (code "93") (name "unconnected-(U7-ADC2-Pad15)") (class "Default")
      (node (ref "U7") (pin "15") (pinfunction "ADC2_15") (pintype "passive"))
    )
    (net (code "94") (name "unconnected-(U7-ADC3-Pad13)") (class "Default")
      (node (ref "U7") (pin "13") (pinfunction "ADC3_13") (pintype "passive"))
    )
    (net (code "95") (name "unconnected-(U7-INT2-Pad9)") (class "Default")
      (node (ref "U7") (pin "9") (pinfunction "INT2_9") (pintype "passive"))
    )
    (net (code "96") (name "unconnected-(U7-NC-Pad2)") (class "Default")
      (node (ref "U7") (pin "2") (pinfunction "NC_2") (pintype "passive"))
    )
    (net (code "97") (name "unconnected-(U7-NC-Pad3)") (class "Default")
      (node (ref "U7") (pin "3") (pinfunction "NC_3") (pintype "passive"))
    )
    (net (code "98") (name "unconnected-(U7-SA0-Pad7)") (class "Default")
      (node (ref "U7") (pin "7") (pinfunction "SA0_7") (pintype "passive"))
    )
  )
)
